# Sheet2.net
KiCad netlist of a schematic drawn in Altium Designer
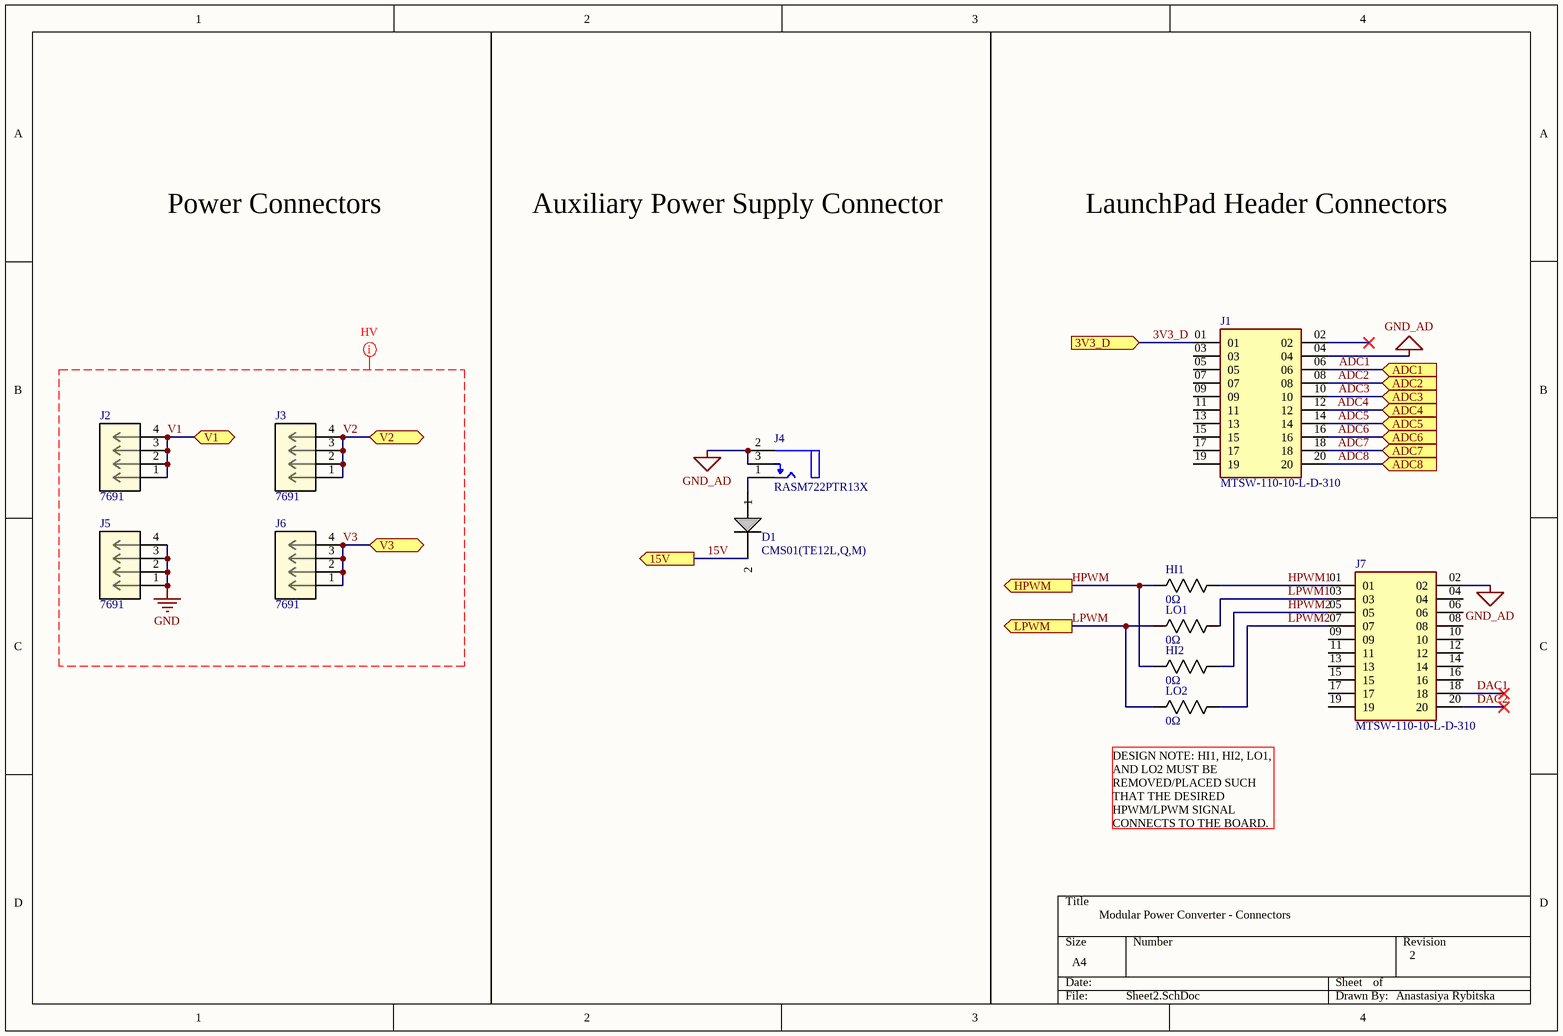
[diagram p0: Sheet2.SchDoc]

(export (version "E")
  (design (tool "Eeschema 10.0.6"))
  (components
    (comp (ref "D1")
      (value "CMS01(TE12L,Q,M)")
      (footprint "M-FLAT_TOS")
      (description "No Description Available")
      (fields (field (name "COPYRIGHT") "Copyright (C) 2022 Ultra Librarian. All rights reserved."))
      (libsource (lib "CMS01_TE12L,Q,M_") (part "CMS01(TE12L,Q,M)"))
    )
    (comp (ref "HI1")
      (value "AC0603FR-070RL")
      (footprint "0603")
      (description "RES SMD 0 OHM JUMPER 1/10W 0603")
      (fields (field (name "RESISTANCE") "0Ω"))
      (libsource (lib "Schlib1") (part "AC0603FR-070RL"))
    )
    (comp (ref "HI2")
      (value "AC0603FR-070RL")
      (footprint "0603")
      (description "RES SMD 0 OHM JUMPER 1/10W 0603")
      (fields (field (name "RESISTANCE") "0Ω"))
      (libsource (lib "Schlib1") (part "AC0603FR-070RL"))
    )
    (comp (ref "J1")
      (value "MTSW-110-10-L-D-310")
      (footprint "SAMTEC_MTSW-110-10-L-D-310")
      (libsource (lib "MTSW-110-10-L-D-310") (part "MTSW-110-10-L-D-310"))
    )
    (comp (ref "J2")
      (value "7691")
      (footprint "CONN_8191_KEY")
      (description "TERM SCREW 6-32 4 PIN PCB")
      (fields (field (name "COPYRIGHT") "Copyright (C) 2022 Ultra Librarian. All rights reserved."))
      (libsource (lib "8191") (part "7691"))
    )
    (comp (ref "J3")
      (value "7691")
      (footprint "CONN_8191_KEY")
      (description "TERM SCREW 6-32 4 PIN PCB")
      (fields (field (name "COPYRIGHT") "Copyright (C) 2022 Ultra Librarian. All rights reserved."))
      (libsource (lib "8191") (part "7691"))
    )
    (comp (ref "J4")
      (value "RASM722PTR13X")
      (footprint "FP-RASM722PTR13X-MFG")
      (description "CONN PWR JACK 2.1X5.5MM SOLDER")
      (libsource (lib "Altium Content Vault") (part "69023cd999ddc70d2a190894d9bbb58"))
    )
    (comp (ref "J5")
      (value "7691")
      (footprint "CONN_8191_KEY")
      (description "TERM SCREW 6-32 4 PIN PCB")
      (fields (field (name "COPYRIGHT") "Copyright (C) 2022 Ultra Librarian. All rights reserved."))
      (libsource (lib "8191") (part "7691"))
    )
    (comp (ref "J6")
      (value "7691")
      (footprint "CONN_8191_KEY")
      (description "TERM SCREW 6-32 4 PIN PCB")
      (fields (field (name "COPYRIGHT") "Copyright (C) 2022 Ultra Librarian. All rights reserved."))
      (libsource (lib "8191") (part "7691"))
    )
    (comp (ref "J7")
      (value "MTSW-110-10-L-D-310")
      (footprint "SAMTEC_MTSW-110-10-L-D-310")
      (libsource (lib "MTSW-110-10-L-D-310") (part "MTSW-110-10-L-D-310"))
    )
    (comp (ref "LO1")
      (value "AC0603FR-070RL")
      (footprint "0603")
      (description "RES SMD 0 OHM JUMPER 1/10W 0603")
      (fields (field (name "RESISTANCE") "0Ω"))
      (libsource (lib "Schlib1") (part "AC0603FR-070RL"))
    )
    (comp (ref "LO2")
      (value "AC0603FR-070RL")
      (footprint "0603")
      (description "RES SMD 0 OHM JUMPER 1/10W 0603")
      (fields (field (name "RESISTANCE") "0Ω"))
      (libsource (lib "Schlib1") (part "AC0603FR-070RL"))
    )
  )
  (nets
    (net (code "1") (name "/3V3_D") (class "Default")
      (node (ref "J1") (pin "01") (pinfunction "01_01") (pintype "passive"))
    )
    (net (code "2") (name "/15V") (class "Default")
      (node (ref "D1") (pin "2") (pinfunction "2_2") (pintype "passive"))
    )
    (net (code "3") (name "/ADC1") (class "Default")
      (node (ref "J1") (pin "06") (pinfunction "06_06") (pintype "passive"))
    )
    (net (code "4") (name "/ADC2") (class "Default")
      (node (ref "J1") (pin "08") (pinfunction "08_08") (pintype "passive"))
    )
    (net (code "5") (name "/ADC3") (class "Default")
      (node (ref "J1") (pin "10") (pinfunction "10_10") (pintype "passive"))
    )
    (net (code "6") (name "/ADC4") (class "Default")
      (node (ref "J1") (pin "12") (pinfunction "12_12") (pintype "passive"))
    )
    (net (code "7") (name "/ADC5") (class "Default")
      (node (ref "J1") (pin "14") (pinfunction "14_14") (pintype "passive"))
    )
    (net (code "8") (name "/ADC6") (class "Default")
      (node (ref "J1") (pin "16") (pinfunction "16_16") (pintype "passive"))
    )
    (net (code "9") (name "/ADC7") (class "Default")
      (node (ref "J1") (pin "18") (pinfunction "18_18") (pintype "passive"))
    )
    (net (code "10") (name "/ADC8") (class "Default")
      (node (ref "J1") (pin "20") (pinfunction "20_20") (pintype "passive"))
    )
    (net (code "11") (name "/DAC1") (class "Default")
      (node (ref "J7") (pin "18") (pinfunction "18_18") (pintype "passive+no_connect"))
    )
    (net (code "12") (name "/DAC2") (class "Default")
      (node (ref "J7") (pin "20") (pinfunction "20_20") (pintype "passive+no_connect"))
    )
    (net (code "13") (name "/HPWM") (class "Default")
      (node (ref "HI1") (pin "1") (pinfunction "1_1") (pintype "passive"))
      (node (ref "HI2") (pin "1") (pinfunction "1_1") (pintype "passive"))
    )
    (net (code "14") (name "/HPWM1") (class "Default")
      (node (ref "HI1") (pin "2") (pinfunction "2_2") (pintype "passive"))
      (node (ref "J7") (pin "01") (pinfunction "01_01") (pintype "passive"))
    )
    (net (code "15") (name "/HPWM2") (class "Default")
      (node (ref "HI2") (pin "2") (pinfunction "2_2") (pintype "passive"))
      (node (ref "J7") (pin "05") (pinfunction "05_05") (pintype "passive"))
    )
    (net (code "16") (name "/LPWM") (class "Default")
      (node (ref "LO1") (pin "1") (pinfunction "1_1") (pintype "passive"))
      (node (ref "LO2") (pin "1") (pinfunction "1_1") (pintype "passive"))
    )
    (net (code "17") (name "/LPWM1") (class "Default")
      (node (ref "J7") (pin "03") (pinfunction "03_03") (pintype "passive"))
      (node (ref "LO1") (pin "2") (pinfunction "2_2") (pintype "passive"))
    )
    (net (code "18") (name "/LPWM2") (class "Default")
      (node (ref "J7") (pin "07") (pinfunction "07_07") (pintype "passive"))
      (node (ref "LO2") (pin "2") (pinfunction "2_2") (pintype "passive"))
    )
    (net (code "19") (name "/V1") (class "Default")
      (node (ref "J2") (pin "1") (pinfunction "1_1") (pintype "passive"))
      (node (ref "J2") (pin "2") (pinfunction "2_2") (pintype "passive"))
      (node (ref "J2") (pin "3") (pinfunction "3_3") (pintype "passive"))
      (node (ref "J2") (pin "4") (pinfunction "4_4") (pintype "passive"))
    )
    (net (code "20") (name "/V2") (class "Default")
      (node (ref "J3") (pin "1") (pinfunction "1_1") (pintype "passive"))
      (node (ref "J3") (pin "2") (pinfunction "2_2") (pintype "passive"))
      (node (ref "J3") (pin "3") (pinfunction "3_3") (pintype "passive"))
      (node (ref "J3") (pin "4") (pinfunction "4_4") (pintype "passive"))
    )
    (net (code "21") (name "/V3") (class "Default")
      (node (ref "J6") (pin "1") (pinfunction "1_1") (pintype "passive"))
      (node (ref "J6") (pin "2") (pinfunction "2_2") (pintype "passive"))
      (node (ref "J6") (pin "3") (pinfunction "3_3") (pintype "passive"))
      (node (ref "J6") (pin "4") (pinfunction "4_4") (pintype "passive"))
    )
    (net (code "22") (name "GND") (class "Default")
      (node (ref "J5") (pin "1") (pinfunction "1_1") (pintype "passive"))
      (node (ref "J5") (pin "2") (pinfunction "2_2") (pintype "passive"))
      (node (ref "J5") (pin "3") (pinfunction "3_3") (pintype "passive"))
      (node (ref "J5") (pin "4") (pinfunction "4_4") (pintype "passive"))
    )
    (net (code "23") (name "GND_AD") (class "Default")
      (node (ref "J1") (pin "04") (pinfunction "04_04") (pintype "passive"))
      (node (ref "J4") (pin "2") (pinfunction "SLEEVE_TERMINAL_2") (pintype "passive"))
      (node (ref "J4") (pin "3") (pinfunction "SHUNT_TERMINAL_3") (pintype "passive"))
      (node (ref "J7") (pin "02") (pinfunction "02_02") (pintype "passive"))
    )
    (net (code "24") (name "Net-(J4-TIP_TERMINAL(CENTER_PIN))") (class "Default")
      (node (ref "D1") (pin "1") (pinfunction "1_1") (pintype "passive"))
      (node (ref "J4") (pin "1") (pinfunction "TIP_TERMINAL(CENTER_PIN)_1") (pintype "passive"))
    )
    (net (code "25") (name "unconnected-(J1-Pad02)") (class "Default")
      (node (ref "J1") (pin "02") (pinfunction "02_02") (pintype "passive+no_connect"))
    )
    (net (code "26") (name "unconnected-(J1-Pad03)") (class "Default")
      (node (ref "J1") (pin "03") (pinfunction "03_03") (pintype "passive"))
    )
    (net (code "27") (name "unconnected-(J1-Pad05)") (class "Default")
      (node (ref "J1") (pin "05") (pinfunction "05_05") (pintype "passive"))
    )
    (net (code "28") (name "unconnected-(J1-Pad07)") (class "Default")
      (node (ref "J1") (pin "07") (pinfunction "07_07") (pintype "passive"))
    )
    (net (code "29") (name "unconnected-(J1-Pad09)") (class "Default")
      (node (ref "J1") (pin "09") (pinfunction "09_09") (pintype "passive"))
    )
    (net (code "30") (name "unconnected-(J1-Pad11)") (class "Default")
      (node (ref "J1") (pin "11") (pinfunction "11_11") (pintype "passive"))
    )
    (net (code "31") (name "unconnected-(J1-Pad13)") (class "Default")
      (node (ref "J1") (pin "13") (pinfunction "13_13") (pintype "passive"))
    )
    (net (code "32") (name "unconnected-(J1-Pad15)") (class "Default")
      (node (ref "J1") (pin "15") (pinfunction "15_15") (pintype "passive"))
    )
    (net (code "33") (name "unconnected-(J1-Pad17)") (class "Default")
      (node (ref "J1") (pin "17") (pinfunction "17_17") (pintype "passive"))
    )
    (net (code "34") (name "unconnected-(J1-Pad19)") (class "Default")
      (node (ref "J1") (pin "19") (pinfunction "19_19") (pintype "passive"))
    )
    (net (code "35") (name "unconnected-(J7-Pad04)") (class "Default")
      (node (ref "J7") (pin "04") (pinfunction "04_04") (pintype "passive"))
    )
    (net (code "36") (name "unconnected-(J7-Pad06)") (class "Default")
      (node (ref "J7") (pin "06") (pinfunction "06_06") (pintype "passive"))
    )
    (net (code "37") (name "unconnected-(J7-Pad08)") (class "Default")
      (node (ref "J7") (pin "08") (pinfunction "08_08") (pintype "passive"))
    )
    (net (code "38") (name "unconnected-(J7-Pad09)") (class "Default")
      (node (ref "J7") (pin "09") (pinfunction "09_09") (pintype "passive"))
    )
    (net (code "39") (name "unconnected-(J7-Pad10)") (class "Default")
      (node (ref "J7") (pin "10") (pinfunction "10_10") (pintype "passive"))
    )
    (net (code "40") (name "unconnected-(J7-Pad11)") (class "Default")
      (node (ref "J7") (pin "11") (pinfunction "11_11") (pintype "passive"))
    )
    (net (code "41") (name "unconnected-(J7-Pad12)") (class "Default")
      (node (ref "J7") (pin "12") (pinfunction "12_12") (pintype "passive"))
    )
    (net (code "42") (name "unconnected-(J7-Pad13)") (class "Default")
      (node (ref "J7") (pin "13") (pinfunction "13_13") (pintype "passive"))
    )
    (net (code "43") (name "unconnected-(J7-Pad14)") (class "Default")
      (node (ref "J7") (pin "14") (pinfunction "14_14") (pintype "passive"))
    )
    (net (code "44") (name "unconnected-(J7-Pad15)") (class "Default")
      (node (ref "J7") (pin "15") (pinfunction "15_15") (pintype "passive"))
    )
    (net (code "45") (name "unconnected-(J7-Pad16)") (class "Default")
      (node (ref "J7") (pin "16") (pinfunction "16_16") (pintype "passive"))
    )
    (net (code "46") (name "unconnected-(J7-Pad17)") (class "Default")
      (node (ref "J7") (pin "17") (pinfunction "17_17") (pintype "passive"))
    )
    (net (code "47") (name "unconnected-(J7-Pad19)") (class "Default")
      (node (ref "J7") (pin "19") (pinfunction "19_19") (pintype "passive"))
    )
  )
)
